# OSSI-1_Battery_Board.net
KiCad netlist of a schematic drawn in EAGLE
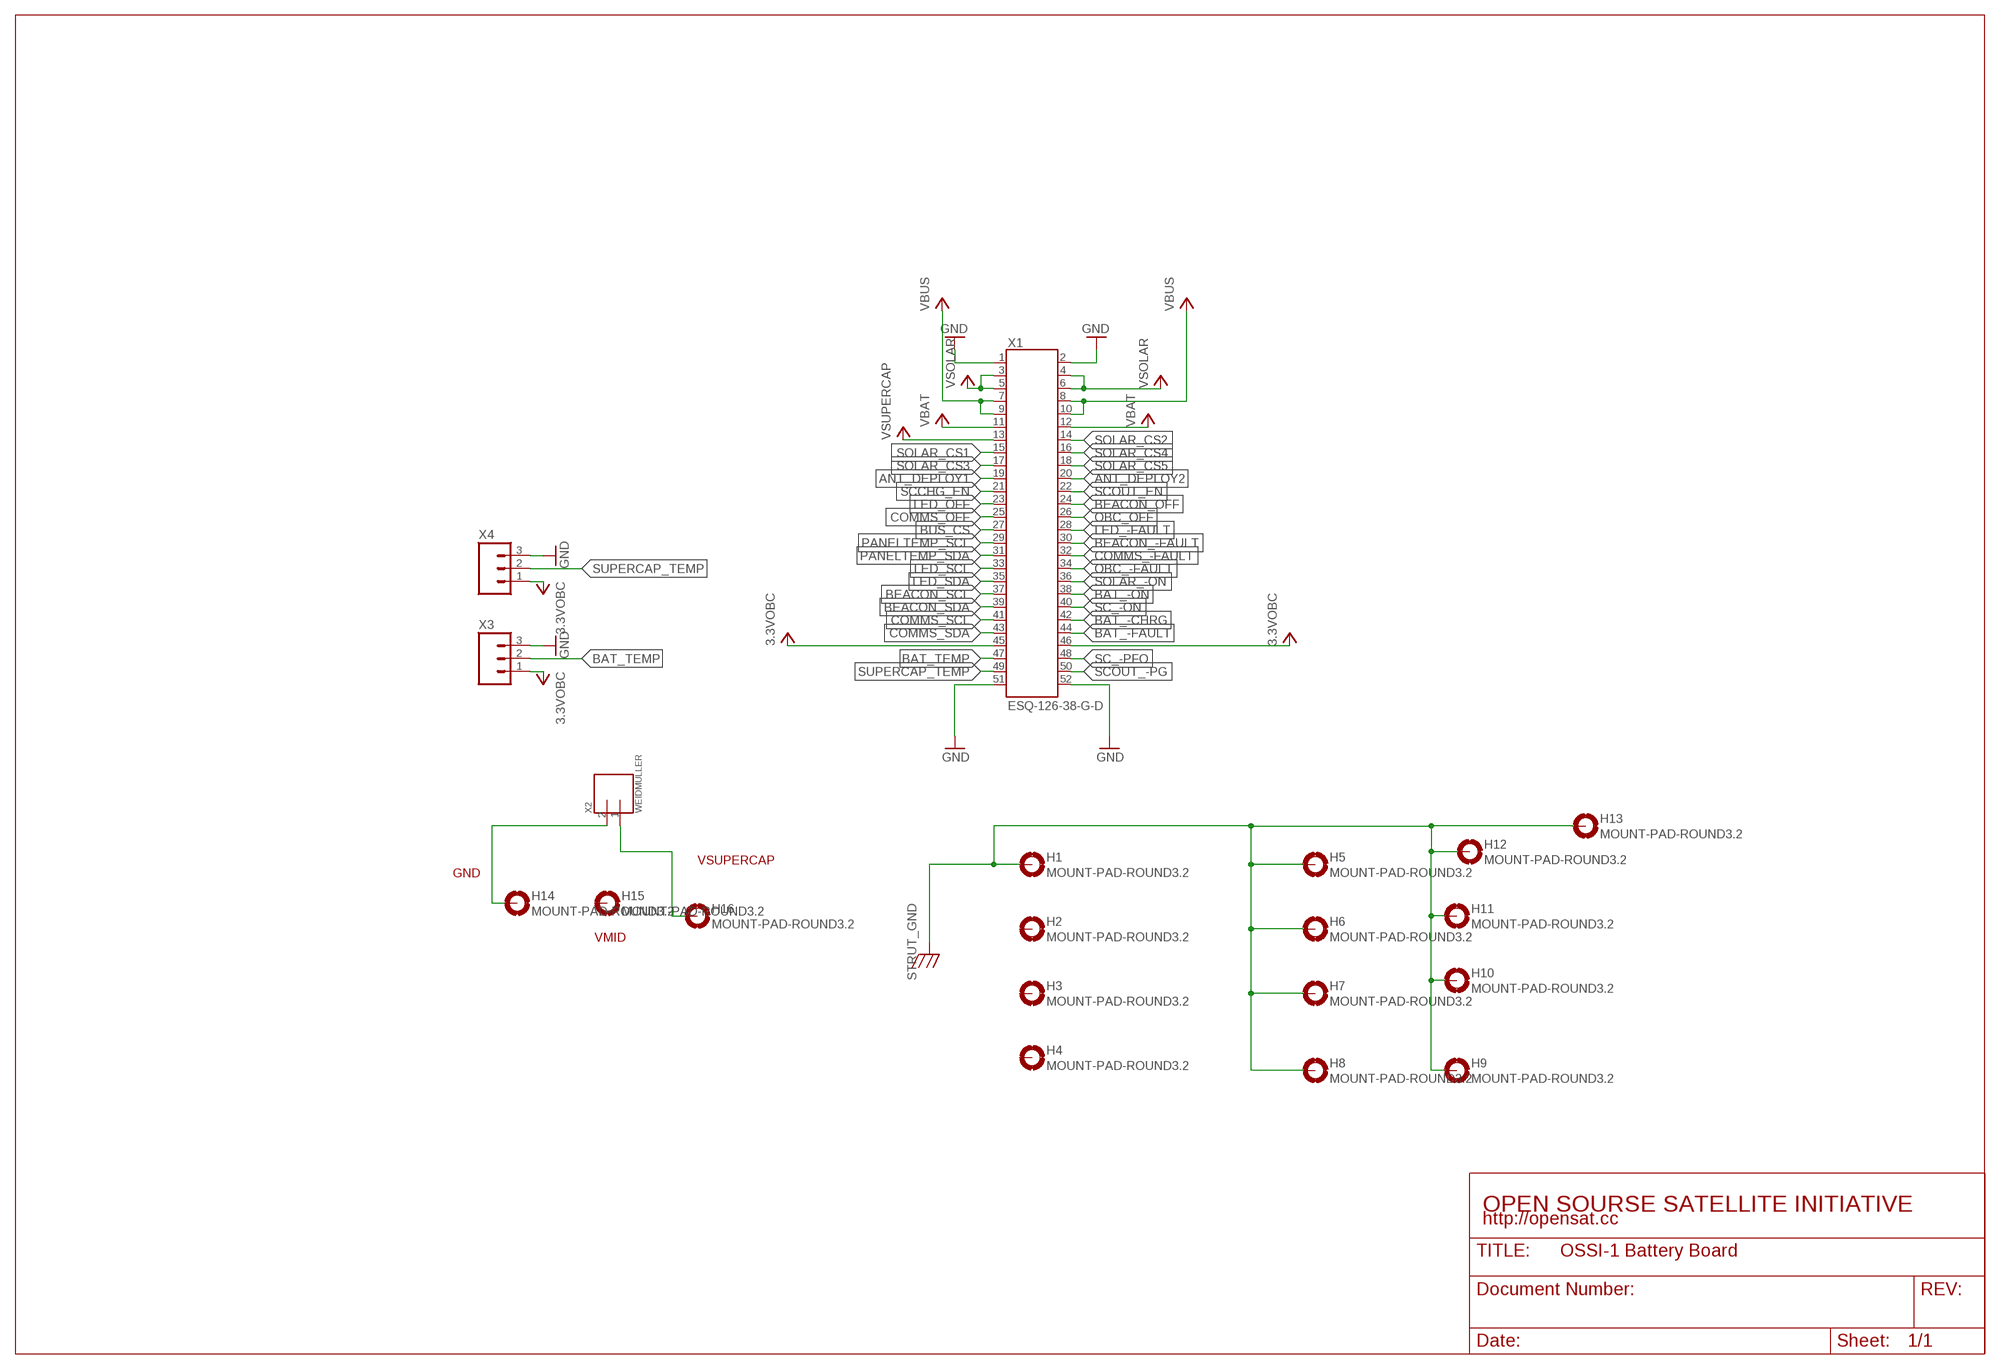
[diagram p0: schematic, sheet 1]

(export (version "E")
  (design (tool "Eeschema 10.0.6"))
  (components
    (comp (ref "H1")
      (value "MOUNT-PAD-ROUND3.2")
      (footprint "eagle-import:3.2-PAD-ROUND")
      (libsource (lib "eagle-import") (part "MOUNT-PAD-ROUND3.2"))
    )
    (comp (ref "H2")
      (value "MOUNT-PAD-ROUND3.2")
      (footprint "eagle-import:3.2-PAD-ROUND")
      (libsource (lib "eagle-import") (part "MOUNT-PAD-ROUND3.2"))
    )
    (comp (ref "H3")
      (value "MOUNT-PAD-ROUND3.2")
      (footprint "eagle-import:3.2-PAD-ROUND")
      (libsource (lib "eagle-import") (part "MOUNT-PAD-ROUND3.2"))
    )
    (comp (ref "H4")
      (value "MOUNT-PAD-ROUND3.2")
      (footprint "eagle-import:3.2-PAD-ROUND")
      (libsource (lib "eagle-import") (part "MOUNT-PAD-ROUND3.2"))
    )
    (comp (ref "H5")
      (value "MOUNT-PAD-ROUND3.2")
      (footprint "eagle-import:3.2-PAD-ROUND")
      (libsource (lib "eagle-import") (part "MOUNT-PAD-ROUND3.2"))
    )
    (comp (ref "H6")
      (value "MOUNT-PAD-ROUND3.2")
      (footprint "eagle-import:3.2-PAD-ROUND")
      (libsource (lib "eagle-import") (part "MOUNT-PAD-ROUND3.2"))
    )
    (comp (ref "H7")
      (value "MOUNT-PAD-ROUND3.2")
      (footprint "eagle-import:3.2-PAD-ROUND")
      (libsource (lib "eagle-import") (part "MOUNT-PAD-ROUND3.2"))
    )
    (comp (ref "H8")
      (value "MOUNT-PAD-ROUND3.2")
      (footprint "eagle-import:3.2-PAD-ROUND")
      (libsource (lib "eagle-import") (part "MOUNT-PAD-ROUND3.2"))
    )
    (comp (ref "H9")
      (value "MOUNT-PAD-ROUND3.2")
      (footprint "eagle-import:3.2-PAD-ROUND")
      (libsource (lib "eagle-import") (part "MOUNT-PAD-ROUND3.2"))
    )
    (comp (ref "H10")
      (value "MOUNT-PAD-ROUND3.2")
      (footprint "eagle-import:3.2-PAD-ROUND")
      (libsource (lib "eagle-import") (part "MOUNT-PAD-ROUND3.2"))
    )
    (comp (ref "H11")
      (value "MOUNT-PAD-ROUND3.2")
      (footprint "eagle-import:3.2-PAD-ROUND")
      (libsource (lib "eagle-import") (part "MOUNT-PAD-ROUND3.2"))
    )
    (comp (ref "H12")
      (value "MOUNT-PAD-ROUND3.2")
      (footprint "eagle-import:3.2-PAD-ROUND")
      (libsource (lib "eagle-import") (part "MOUNT-PAD-ROUND3.2"))
    )
    (comp (ref "H13")
      (value "MOUNT-PAD-ROUND3.2")
      (footprint "eagle-import:3.2-PAD-ROUND")
      (libsource (lib "eagle-import") (part "MOUNT-PAD-ROUND3.2"))
    )
    (comp (ref "H14")
      (value "MOUNT-PAD-ROUND3.2")
      (footprint "eagle-import:3.2-PAD-ROUND")
      (libsource (lib "eagle-import") (part "MOUNT-PAD-ROUND3.2"))
    )
    (comp (ref "H15")
      (value "MOUNT-PAD-ROUND3.2")
      (footprint "eagle-import:3.2-PAD-ROUND")
      (libsource (lib "eagle-import") (part "MOUNT-PAD-ROUND3.2"))
    )
    (comp (ref "H16")
      (value "MOUNT-PAD-ROUND3.2")
      (footprint "eagle-import:3.2-PAD-ROUND")
      (libsource (lib "eagle-import") (part "MOUNT-PAD-ROUND3.2"))
    )
    (comp (ref "X1")
      (value "ESQ-126-38-G-D")
      (footprint "eagle-import:ESQ-126-XX-X-D")
      (libsource (lib "eagle-import") (part "ESQ-126-38-G-D"))
    )
    (comp (ref "X2")
      (value "WEIDMULLER")
      (footprint "eagle-import:WEIDMULLER1760490000")
      (libsource (lib "eagle-import") (part "WEIDMULLER"))
    )
    (comp (ref "X3")
      (value "M03PTH")
      (footprint "eagle-import:1X03")
      (libsource (lib "eagle-import") (part "M03PTH"))
    )
    (comp (ref "X4")
      (value "M03PTH")
      (footprint "eagle-import:1X03")
      (libsource (lib "eagle-import") (part "M03PTH"))
    )
  )
  (nets
    (net (code "1") (name "3.3VOBC") (class "Default")
      (node (ref "X1") (pin "45") (pinfunction "45_45") (pintype "bidirectional"))
      (node (ref "X1") (pin "46") (pinfunction "46_46") (pintype "bidirectional"))
      (node (ref "X3") (pin "1") (pinfunction "1_1") (pintype "passive"))
      (node (ref "X4") (pin "1") (pinfunction "1_1") (pintype "passive"))
    )
    (net (code "2") (name "ANT_DEPLOY1") (class "Default")
      (node (ref "X1") (pin "19") (pinfunction "19_19") (pintype "bidirectional"))
    )
    (net (code "3") (name "ANT_DEPLOY2") (class "Default")
      (node (ref "X1") (pin "20") (pinfunction "20_20") (pintype "bidirectional"))
    )
    (net (code "4") (name "BAT_-CHRG") (class "Default")
      (node (ref "X1") (pin "42") (pinfunction "42_42") (pintype "bidirectional"))
    )
    (net (code "5") (name "BAT_-FAULT") (class "Default")
      (node (ref "X1") (pin "44") (pinfunction "44_44") (pintype "bidirectional"))
    )
    (net (code "6") (name "BAT_-ON") (class "Default")
      (node (ref "X1") (pin "38") (pinfunction "38_38") (pintype "bidirectional"))
    )
    (net (code "7") (name "BAT_TEMP") (class "Default")
      (node (ref "X1") (pin "47") (pinfunction "47_47") (pintype "bidirectional"))
      (node (ref "X3") (pin "2") (pinfunction "2_2") (pintype "passive"))
    )
    (net (code "8") (name "BEACON_-FAULT") (class "Default")
      (node (ref "X1") (pin "30") (pinfunction "30_30") (pintype "bidirectional"))
    )
    (net (code "9") (name "BEACON_OFF") (class "Default")
      (node (ref "X1") (pin "24") (pinfunction "24_24") (pintype "bidirectional"))
    )
    (net (code "10") (name "BEACON_SCL") (class "Default")
      (node (ref "X1") (pin "37") (pinfunction "37_37") (pintype "bidirectional"))
    )
    (net (code "11") (name "BEACON_SDA") (class "Default")
      (node (ref "X1") (pin "39") (pinfunction "39_39") (pintype "bidirectional"))
    )
    (net (code "12") (name "BUS_CS") (class "Default")
      (node (ref "X1") (pin "27") (pinfunction "27_27") (pintype "bidirectional"))
    )
    (net (code "13") (name "COMMS_-FAULT") (class "Default")
      (node (ref "X1") (pin "32") (pinfunction "32_32") (pintype "bidirectional"))
    )
    (net (code "14") (name "COMMS_OFF") (class "Default")
      (node (ref "X1") (pin "25") (pinfunction "25_25") (pintype "bidirectional"))
    )
    (net (code "15") (name "COMMS_SCL") (class "Default")
      (node (ref "X1") (pin "41") (pinfunction "41_41") (pintype "bidirectional"))
    )
    (net (code "16") (name "COMMS_SDA") (class "Default")
      (node (ref "X1") (pin "43") (pinfunction "43_43") (pintype "bidirectional"))
    )
    (net (code "17") (name "GND") (class "Default")
      (node (ref "X1") (pin "1") (pinfunction "1_1") (pintype "bidirectional"))
      (node (ref "X1") (pin "2") (pinfunction "2_2") (pintype "bidirectional"))
      (node (ref "X1") (pin "51") (pinfunction "51_51") (pintype "bidirectional"))
      (node (ref "X1") (pin "52") (pinfunction "52_52") (pintype "bidirectional"))
      (node (ref "X3") (pin "3") (pinfunction "3_3") (pintype "passive"))
      (node (ref "X4") (pin "3") (pinfunction "3_3") (pintype "passive"))
    )
    (net (code "18") (name "LED_-FAULT") (class "Default")
      (node (ref "X1") (pin "28") (pinfunction "28_28") (pintype "bidirectional"))
    )
    (net (code "19") (name "LED_OFF") (class "Default")
      (node (ref "X1") (pin "23") (pinfunction "23_23") (pintype "bidirectional"))
    )
    (net (code "20") (name "LED_SCL") (class "Default")
      (node (ref "X1") (pin "33") (pinfunction "33_33") (pintype "bidirectional"))
    )
    (net (code "21") (name "LED_SDA") (class "Default")
      (node (ref "X1") (pin "35") (pinfunction "35_35") (pintype "bidirectional"))
    )
    (net (code "22") (name "Net-(H14-MOUNT)") (class "Default")
      (node (ref "H14") (pin "B3,2") (pinfunction "MOUNT_B3,2") (pintype "passive"))
      (node (ref "X2") (pin "2") (pinfunction "2_2") (pintype "bidirectional"))
    )
    (net (code "23") (name "Net-(H16-MOUNT)") (class "Default")
      (node (ref "H16") (pin "B3,2") (pinfunction "MOUNT_B3,2") (pintype "passive"))
      (node (ref "X2") (pin "1") (pinfunction "1_1") (pintype "bidirectional"))
    )
    (net (code "24") (name "OBC_-FAULT") (class "Default")
      (node (ref "X1") (pin "34") (pinfunction "34_34") (pintype "bidirectional"))
    )
    (net (code "25") (name "OBC_OFF") (class "Default")
      (node (ref "X1") (pin "26") (pinfunction "26_26") (pintype "bidirectional"))
    )
    (net (code "26") (name "PANELTEMP_SCL") (class "Default")
      (node (ref "X1") (pin "29") (pinfunction "29_29") (pintype "bidirectional"))
    )
    (net (code "27") (name "PANELTEMP_SDA") (class "Default")
      (node (ref "X1") (pin "31") (pinfunction "31_31") (pintype "bidirectional"))
    )
    (net (code "28") (name "SCCHG_EN") (class "Default")
      (node (ref "X1") (pin "21") (pinfunction "21_21") (pintype "bidirectional"))
    )
    (net (code "29") (name "SCOUT_-PG") (class "Default")
      (node (ref "X1") (pin "50") (pinfunction "50_50") (pintype "bidirectional"))
    )
    (net (code "30") (name "SCOUT_EN") (class "Default")
      (node (ref "X1") (pin "22") (pinfunction "22_22") (pintype "bidirectional"))
    )
    (net (code "31") (name "SC_-ON") (class "Default")
      (node (ref "X1") (pin "40") (pinfunction "40_40") (pintype "bidirectional"))
    )
    (net (code "32") (name "SC_-PFO") (class "Default")
      (node (ref "X1") (pin "48") (pinfunction "48_48") (pintype "bidirectional"))
    )
    (net (code "33") (name "SOLAR_-ON") (class "Default")
      (node (ref "X1") (pin "36") (pinfunction "36_36") (pintype "bidirectional"))
    )
    (net (code "34") (name "SOLAR_CS1") (class "Default")
      (node (ref "X1") (pin "15") (pinfunction "15_15") (pintype "bidirectional"))
    )
    (net (code "35") (name "SOLAR_CS2") (class "Default")
      (node (ref "X1") (pin "14") (pinfunction "14_14") (pintype "bidirectional"))
    )
    (net (code "36") (name "SOLAR_CS3") (class "Default")
      (node (ref "X1") (pin "17") (pinfunction "17_17") (pintype "bidirectional"))
    )
    (net (code "37") (name "SOLAR_CS4") (class "Default")
      (node (ref "X1") (pin "16") (pinfunction "16_16") (pintype "bidirectional"))
    )
    (net (code "38") (name "SOLAR_CS5") (class "Default")
      (node (ref "X1") (pin "18") (pinfunction "18_18") (pintype "bidirectional"))
    )
    (net (code "39") (name "STRUT_GND") (class "Default")
      (node (ref "H1") (pin "B3,2") (pinfunction "MOUNT_B3,2") (pintype "passive"))
      (node (ref "H10") (pin "B3,2") (pinfunction "MOUNT_B3,2") (pintype "passive"))
      (node (ref "H11") (pin "B3,2") (pinfunction "MOUNT_B3,2") (pintype "passive"))
      (node (ref "H12") (pin "B3,2") (pinfunction "MOUNT_B3,2") (pintype "passive"))
      (node (ref "H13") (pin "B3,2") (pinfunction "MOUNT_B3,2") (pintype "passive"))
      (node (ref "H5") (pin "B3,2") (pinfunction "MOUNT_B3,2") (pintype "passive"))
      (node (ref "H6") (pin "B3,2") (pinfunction "MOUNT_B3,2") (pintype "passive"))
      (node (ref "H7") (pin "B3,2") (pinfunction "MOUNT_B3,2") (pintype "passive"))
      (node (ref "H8") (pin "B3,2") (pinfunction "MOUNT_B3,2") (pintype "passive"))
      (node (ref "H9") (pin "B3,2") (pinfunction "MOUNT_B3,2") (pintype "passive"))
    )
    (net (code "40") (name "SUPERCAP_TEMP") (class "Default")
      (node (ref "X1") (pin "49") (pinfunction "49_49") (pintype "bidirectional"))
      (node (ref "X4") (pin "2") (pinfunction "2_2") (pintype "passive"))
    )
    (net (code "41") (name "VBAT") (class "Default")
      (node (ref "X1") (pin "11") (pinfunction "11_11") (pintype "bidirectional"))
      (node (ref "X1") (pin "12") (pinfunction "12_12") (pintype "bidirectional"))
    )
    (net (code "42") (name "VBUS") (class "Default")
      (node (ref "X1") (pin "10") (pinfunction "10_10") (pintype "bidirectional"))
      (node (ref "X1") (pin "7") (pinfunction "7_7") (pintype "bidirectional"))
      (node (ref "X1") (pin "8") (pinfunction "8_8") (pintype "bidirectional"))
      (node (ref "X1") (pin "9") (pinfunction "9_9") (pintype "bidirectional"))
    )
    (net (code "43") (name "VSOLAR") (class "Default")
      (node (ref "X1") (pin "3") (pinfunction "3_3") (pintype "bidirectional"))
      (node (ref "X1") (pin "4") (pinfunction "4_4") (pintype "bidirectional"))
      (node (ref "X1") (pin "5") (pinfunction "5_5") (pintype "bidirectional"))
      (node (ref "X1") (pin "6") (pinfunction "6_6") (pintype "bidirectional"))
    )
    (net (code "44") (name "VSUPERCAP") (class "Default")
      (node (ref "X1") (pin "13") (pinfunction "13_13") (pintype "bidirectional"))
    )
    (net (code "45") (name "unconnected-(H2-MOUNT-PadB3,2)") (class "Default")
      (node (ref "H2") (pin "B3,2") (pinfunction "MOUNT_B3,2") (pintype "passive"))
    )
    (net (code "46") (name "unconnected-(H3-MOUNT-PadB3,2)") (class "Default")
      (node (ref "H3") (pin "B3,2") (pinfunction "MOUNT_B3,2") (pintype "passive"))
    )
    (net (code "47") (name "unconnected-(H4-MOUNT-PadB3,2)") (class "Default")
      (node (ref "H4") (pin "B3,2") (pinfunction "MOUNT_B3,2") (pintype "passive"))
    )
    (net (code "48") (name "unconnected-(H15-MOUNT-PadB3,2)") (class "Default")
      (node (ref "H15") (pin "B3,2") (pinfunction "MOUNT_B3,2") (pintype "passive"))
    )
  )
)
